# 11_-_GMAC1-SODIMM.net
KiCad netlist of a schematic drawn in Altium Designer
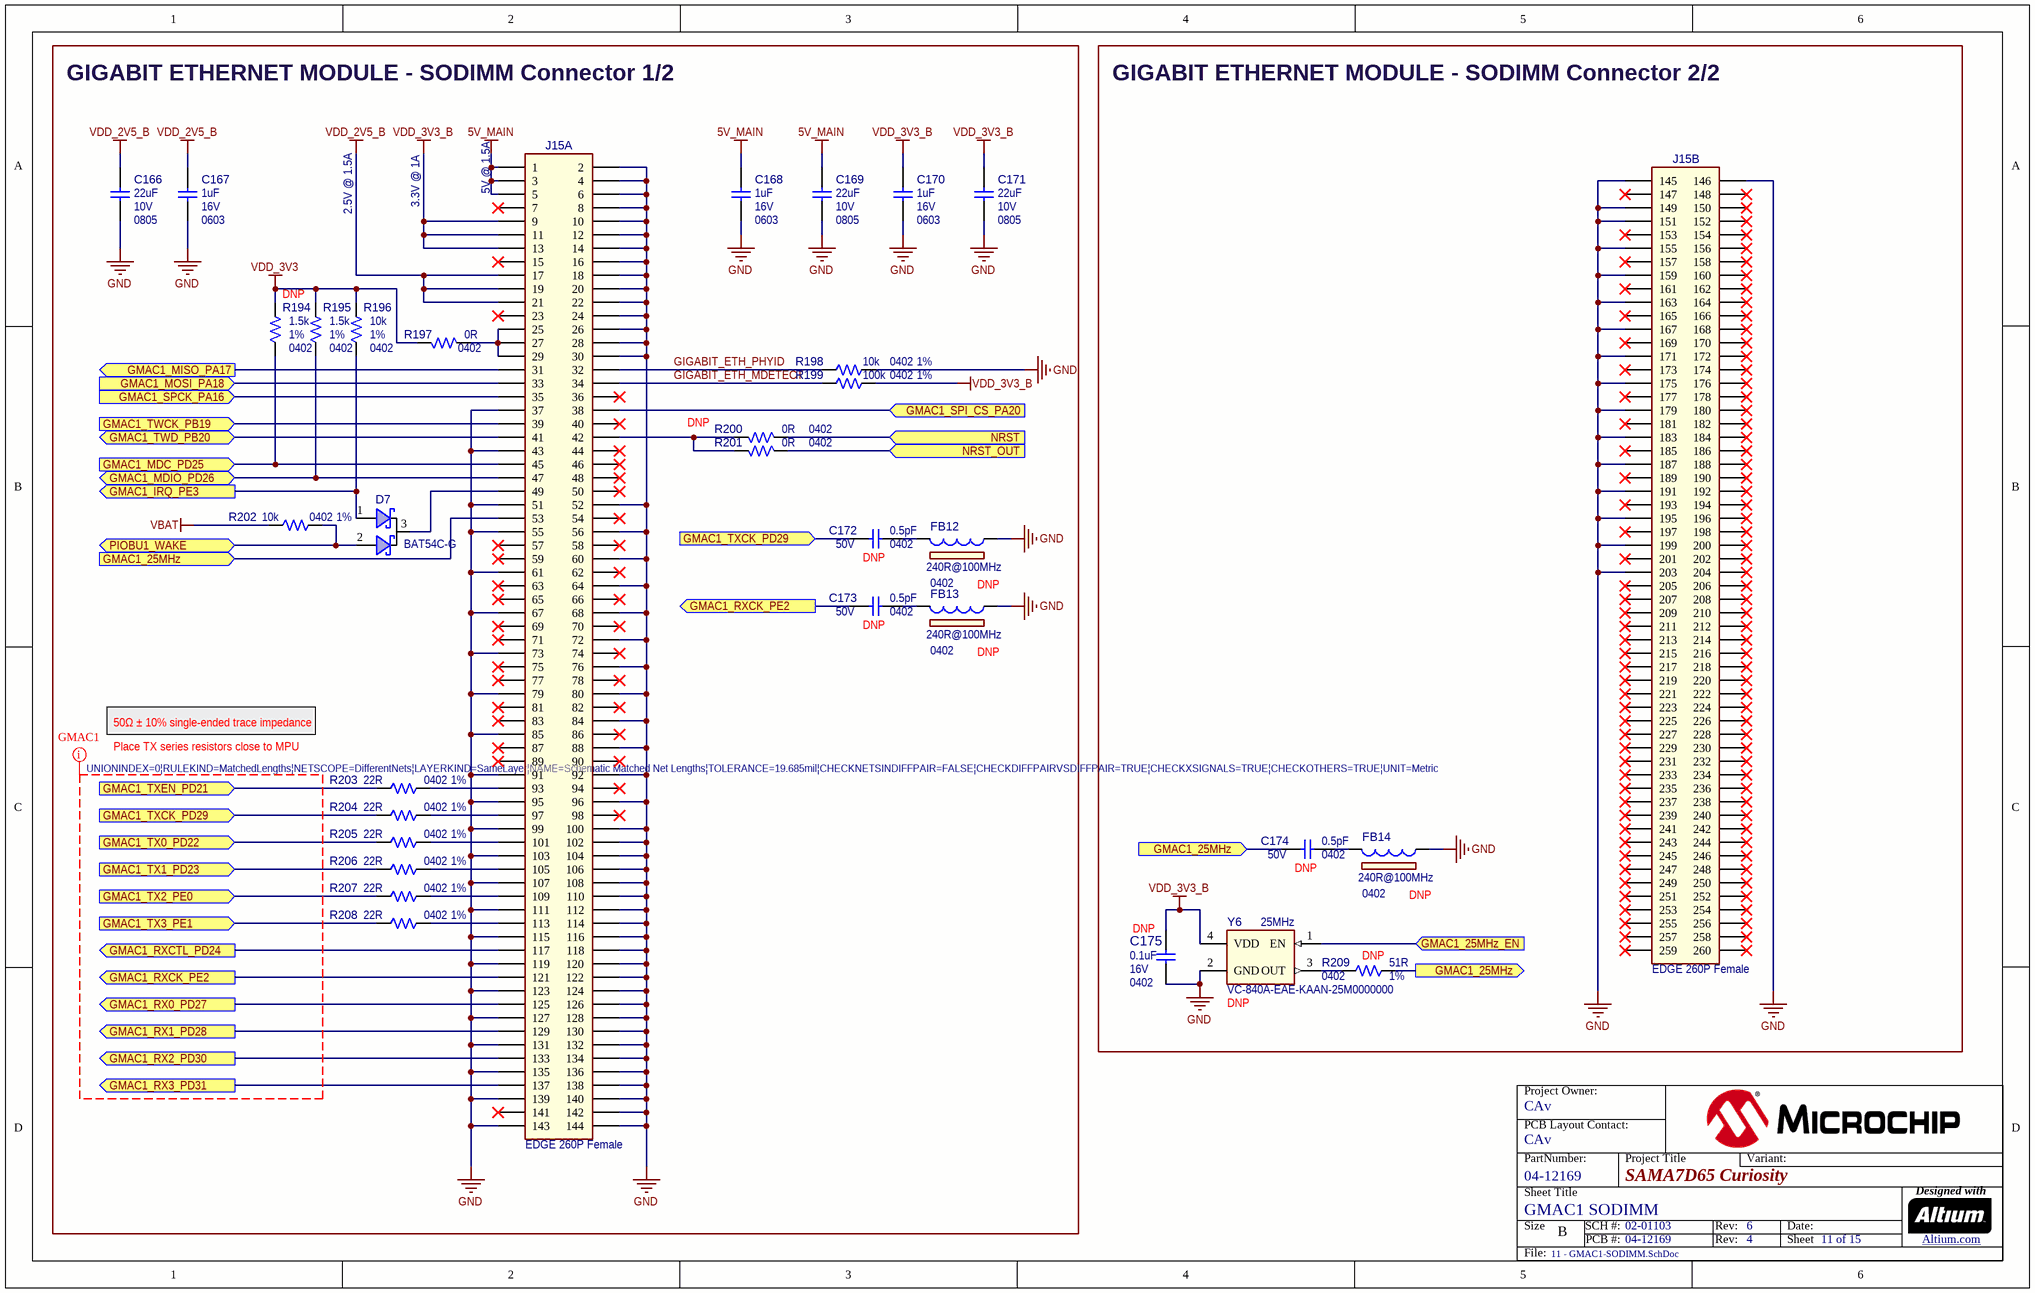
[diagram p0: 11 - GMAC1-SODIMM.SchDoc]

(export (version "E")
  (design (tool "Eeschema 10.0.6"))
  (components
    (comp (ref "C166")
      (value "22uF")
      (footprint "CAP_C_0805")
      (fields
        (field (name "VOLTAGE") "10V")
        (field (name "PACKAGE") "0805")
        (field (name "TOLERANCE") "20%")
        (field (name "Comment") "Capacitor NP")
        (field (name "OWNER") "Razvan Cristescu")
      )
      (libsource (lib "MCHP-CDB") (part "Capacitor NP"))
    )
    (comp (ref "C167")
      (value "1uF")
      (footprint "CAP_C_0603")
      (fields
        (field (name "VOLTAGE") "16V")
        (field (name "PACKAGE") "0603")
        (field (name "TOLERANCE") "10%")
        (field (name "Comment") "Capacitor NP")
      )
      (libsource (lib "MCHP-CDB") (part "Capacitor NP"))
    )
    (comp (ref "C168")
      (value "1uF")
      (footprint "CAP_C_0603")
      (fields
        (field (name "VOLTAGE") "16V")
        (field (name "PACKAGE") "0603")
        (field (name "TOLERANCE") "10%")
        (field (name "Comment") "Capacitor NP")
      )
      (libsource (lib "MCHP-CDB") (part "Capacitor NP"))
    )
    (comp (ref "C169")
      (value "22uF")
      (footprint "CAP_C_0805")
      (fields
        (field (name "VOLTAGE") "10V")
        (field (name "PACKAGE") "0805")
        (field (name "TOLERANCE") "20%")
        (field (name "Comment") "Capacitor NP")
        (field (name "OWNER") "Razvan Cristescu")
      )
      (libsource (lib "MCHP-CDB") (part "Capacitor NP"))
    )
    (comp (ref "C170")
      (value "1uF")
      (footprint "CAP_C_0603")
      (fields
        (field (name "VOLTAGE") "16V")
        (field (name "PACKAGE") "0603")
        (field (name "TOLERANCE") "10%")
        (field (name "Comment") "Capacitor NP")
      )
      (libsource (lib "MCHP-CDB") (part "Capacitor NP"))
    )
    (comp (ref "C171")
      (value "22uF")
      (footprint "CAP_C_0805")
      (fields
        (field (name "VOLTAGE") "10V")
        (field (name "PACKAGE") "0805")
        (field (name "TOLERANCE") "20%")
        (field (name "Comment") "Capacitor NP")
        (field (name "OWNER") "Razvan Cristescu")
      )
      (libsource (lib "MCHP-CDB") (part "Capacitor NP"))
    )
    (comp (ref "C172")
      (value "0.5pF")
      (footprint "CAP_C_0402")
      (fields
        (field (name "VOLTAGE") "50V")
        (field (name "PACKAGE") "0402")
        (field (name "TOLERANCE") "0.25pF")
        (field (name "POPULATED") "DNP")
        (field (name "Comment") "Capacitor NP")
      )
      (libsource (lib "MCHP-CDB") (part "Capacitor NP"))
    )
    (comp (ref "C173")
      (value "0.5pF")
      (footprint "CAP_C_0402")
      (fields
        (field (name "VOLTAGE") "50V")
        (field (name "PACKAGE") "0402")
        (field (name "TOLERANCE") "0.25pF")
        (field (name "POPULATED") "DNP")
        (field (name "Comment") "Capacitor NP")
      )
      (libsource (lib "MCHP-CDB") (part "Capacitor NP"))
    )
    (comp (ref "C174")
      (value "0.5pF")
      (footprint "CAP_C_0402")
      (fields
        (field (name "VOLTAGE") "50V")
        (field (name "PACKAGE") "0402")
        (field (name "TOLERANCE") "0.25pF")
        (field (name "POPULATED") "DNP")
        (field (name "Comment") "Capacitor NP")
      )
      (libsource (lib "MCHP-CDB") (part "Capacitor NP"))
    )
    (comp (ref "C175")
      (value "0.1uF")
      (footprint "CAP_C_0402")
      (fields
        (field (name "VOLTAGE") "16V")
        (field (name "PACKAGE") "0402")
        (field (name "TOLERANCE") "10%")
        (field (name "POPULATED") "DNP")
        (field (name "Comment") "Capacitor NP")
        (field (name "OWNER") "Sompoch Loboonlert")
      )
      (libsource (lib "MCHP-CDB") (part "Capacitor NP"))
    )
    (comp (ref "D7")
      (value "BAT54C-G")
      (footprint "SOT-23-3")
      (fields
        (field (name "POWER") "225mW")
        (field (name "Comment") "Diode Schottky Dual CK")
        (field (name "OWNER") "Cristina Salanti")
      )
      (libsource (lib "MCHP-CDB") (part "Diode Schottky Dual CK"))
    )
    (comp (ref "FB12")
      (value "240R@100MHz")
      (footprint "IND_C_0402")
      (fields
        (field (name "PACKAGE") "0402")
        (field (name "POPULATED") "DNP")
        (field (name "Comment") "Ferrite Bead")
        (field (name "OWNER") "Joerg Buehrer")
      )
      (libsource (lib "MCHP-CDB") (part "Ferrite Bead"))
    )
    (comp (ref "FB13")
      (value "240R@100MHz")
      (footprint "IND_C_0402")
      (fields
        (field (name "PACKAGE") "0402")
        (field (name "POPULATED") "DNP")
        (field (name "Comment") "Ferrite Bead")
        (field (name "OWNER") "Joerg Buehrer")
      )
      (libsource (lib "MCHP-CDB") (part "Ferrite Bead"))
    )
    (comp (ref "FB14")
      (value "240R@100MHz")
      (footprint "IND_C_0402")
      (fields
        (field (name "PACKAGE") "0402")
        (field (name "POPULATED") "DNP")
        (field (name "Comment") "Ferrite Bead")
        (field (name "OWNER") "Joerg Buehrer")
      )
      (libsource (lib "MCHP-CDB") (part "Ferrite Bead"))
    )
    (comp (ref "J15")
      (value "EDGE 260P Female")
      (footprint "CON_EDGE-CARD_DDR4_260P_SODIMM_2309413")
      (fields (field (name "Comment") "Header 2x130 EDGE CARD") (field (name "OWNER") "Sam Charles"))
      (libsource (lib "MCHP-CDB") (part "Header 2x130 EDGE CARD"))
    )
    (comp (ref "R194")
      (value "1.5k")
      (footprint "RES_C_0402")
      (description "Resistor")
      (fields
        (field (name "PACKAGE") "0402")
        (field (name "TOLERANCE") "1%")
        (field (name "POWER") "1/10W")
        (field (name "POPULATED") "DNP")
        (field (name "OWNER") "Gabor Bihari")
      )
      (libsource (lib "") (part "Resistor_1"))
    )
    (comp (ref "R195")
      (value "1.5k")
      (footprint "RES_C_0402")
      (description "Resistor")
      (fields
        (field (name "PACKAGE") "0402")
        (field (name "TOLERANCE") "1%")
        (field (name "POWER") "1/10W")
        (field (name "OWNER") "Gabor Bihari")
      )
      (libsource (lib "") (part "Resistor_1"))
    )
    (comp (ref "R196")
      (value "10k")
      (footprint "RES_C_0402")
      (description "Resistor")
      (fields
        (field (name "PACKAGE") "0402")
        (field (name "TOLERANCE") "1%")
        (field (name "VOLTAGE") "50V")
        (field (name "POWER") "1/10W")
        (field (name "OWNER") "Brent Lanphear")
      )
      (libsource (lib "MCHP-CDB") (part "Resistor"))
    )
    (comp (ref "R197")
      (value "0R")
      (footprint "RES_C_0402")
      (description "Resistor")
      (fields
        (field (name "PACKAGE") "0402")
        (field (name "POWER") "1/16W")
        (field (name "OWNER") "Sompoch Loboonlert")
      )
      (libsource (lib "") (part "Resistor_1"))
    )
    (comp (ref "R198")
      (value "10k")
      (footprint "RES_C_0402")
      (description "Resistor")
      (fields
        (field (name "PACKAGE") "0402")
        (field (name "TOLERANCE") "1%")
        (field (name "VOLTAGE") "50V")
        (field (name "POWER") "1/10W")
        (field (name "OWNER") "Brent Lanphear")
      )
      (libsource (lib "MCHP-CDB") (part "Resistor"))
    )
    (comp (ref "R199")
      (value "100k")
      (footprint "RES_C_0402")
      (description "Resistor")
      (fields
        (field (name "PACKAGE") "0402")
        (field (name "TOLERANCE") "1%")
        (field (name "VOLTAGE") "50V")
        (field (name "POWER") "1/10W")
        (field (name "OWNER") "Tad Ahlvers")
      )
      (libsource (lib "") (part "Resistor_1"))
    )
    (comp (ref "R200")
      (value "0R")
      (footprint "RES_C_0402")
      (description "Resistor")
      (fields
        (field (name "PACKAGE") "0402")
        (field (name "POWER") "1/16W")
        (field (name "POPULATED") "DNP")
        (field (name "OWNER") "Sompoch Loboonlert")
      )
      (libsource (lib "") (part "Resistor_1"))
    )
    (comp (ref "R201")
      (value "0R")
      (footprint "RES_C_0402")
      (description "Resistor")
      (fields
        (field (name "PACKAGE") "0402")
        (field (name "POWER") "1/16W")
        (field (name "OWNER") "Sompoch Loboonlert")
      )
      (libsource (lib "") (part "Resistor_1"))
    )
    (comp (ref "R202")
      (value "10k")
      (footprint "RES_C_0402")
      (description "Resistor")
      (fields
        (field (name "PACKAGE") "0402")
        (field (name "TOLERANCE") "1%")
        (field (name "VOLTAGE") "50V")
        (field (name "POWER") "1/10W")
        (field (name "OWNER") "Brent Lanphear")
      )
      (libsource (lib "MCHP-CDB") (part "Resistor"))
    )
    (comp (ref "R203")
      (value "22R")
      (footprint "RES_C_0402")
      (description "Resistor")
      (fields
        (field (name "PACKAGE") "0402")
        (field (name "TOLERANCE") "1%")
        (field (name "POWER") "1/10W")
        (field (name "OWNER") "Mike Ragsdale")
      )
      (libsource (lib "MCHP-CDB") (part "Resistor"))
    )
    (comp (ref "R204")
      (value "22R")
      (footprint "RES_C_0402")
      (description "Resistor")
      (fields
        (field (name "PACKAGE") "0402")
        (field (name "TOLERANCE") "1%")
        (field (name "POWER") "1/10W")
        (field (name "OWNER") "Mike Ragsdale")
      )
      (libsource (lib "MCHP-CDB") (part "Resistor"))
    )
    (comp (ref "R205")
      (value "22R")
      (footprint "RES_C_0402")
      (description "Resistor")
      (fields
        (field (name "PACKAGE") "0402")
        (field (name "TOLERANCE") "1%")
        (field (name "POWER") "1/10W")
        (field (name "OWNER") "Mike Ragsdale")
      )
      (libsource (lib "MCHP-CDB") (part "Resistor"))
    )
    (comp (ref "R206")
      (value "22R")
      (footprint "RES_C_0402")
      (description "Resistor")
      (fields
        (field (name "PACKAGE") "0402")
        (field (name "TOLERANCE") "1%")
        (field (name "POWER") "1/10W")
        (field (name "OWNER") "Mike Ragsdale")
      )
      (libsource (lib "MCHP-CDB") (part "Resistor"))
    )
    (comp (ref "R207")
      (value "22R")
      (footprint "RES_C_0402")
      (description "Resistor")
      (fields
        (field (name "PACKAGE") "0402")
        (field (name "TOLERANCE") "1%")
        (field (name "POWER") "1/10W")
        (field (name "OWNER") "Mike Ragsdale")
      )
      (libsource (lib "MCHP-CDB") (part "Resistor"))
    )
    (comp (ref "R208")
      (value "22R")
      (footprint "RES_C_0402")
      (description "Resistor")
      (fields
        (field (name "PACKAGE") "0402")
        (field (name "TOLERANCE") "1%")
        (field (name "POWER") "1/10W")
        (field (name "OWNER") "Mike Ragsdale")
      )
      (libsource (lib "MCHP-CDB") (part "Resistor"))
    )
    (comp (ref "R209")
      (value "51R")
      (footprint "RES_C_0402")
      (description "Resistor")
      (fields
        (field (name "PACKAGE") "0402")
        (field (name "TOLERANCE") "1%")
        (field (name "VOLTAGE") "50V")
        (field (name "POWER") "1/5W")
        (field (name "POPULATED") "DNP")
        (field (name "OWNER") "Dragos Danaila")
      )
      (libsource (lib "MCHP-CDB") (part "Resistor"))
    )
    (comp (ref "Y6")
      (value "25MHz")
      (footprint "CRYSTAL_VC-840")
      (fields
        (field (name "MANUFACTURER PART NUMBER 1") "VC-840A-EAE-KAAN-25M0000000")
        (field (name "POPULATED") "DNP")
        (field (name "Comment") "OSCILLATOR 4 Pins")
        (field (name "OWNER") "Pilar Alcaine")
      )
      (libsource (lib "MCHP-CDB") (part "OSCILLATOR 4 Pins"))
    )
  )
  (nets
    (net (code "1") (name "/GIGABIT_ETH_MDETECT") (class "Default")
      (node (ref "J15") (pin "34") (pinfunction "34_34") (pintype "passive"))
      (node (ref "R199") (pin "2") (pinfunction "2_2") (pintype "passive"))
    )
    (net (code "2") (name "/GIGABIT_ETH_PHYID") (class "Default")
      (node (ref "J15") (pin "32") (pinfunction "32_32") (pintype "passive"))
      (node (ref "R198") (pin "2") (pinfunction "2_2") (pintype "passive"))
    )
    (net (code "3") (name "/GMAC1_25MHz") (class "Default")
      (node (ref "C174") (pin "2") (pinfunction "2_2") (pintype "passive"))
      (node (ref "J15") (pin "53") (pinfunction "53_53") (pintype "passive"))
      (node (ref "R209") (pin "1") (pinfunction "1_1") (pintype "passive"))
    )
    (net (code "4") (name "/GMAC1_25MHz_EN") (class "Default")
      (node (ref "Y6") (pin "1") (pinfunction "EN_1") (pintype "input"))
    )
    (net (code "5") (name "/GMAC1_IRQ_PE3") (class "Default")
      (node (ref "D7") (pin "1") (pinfunction "A_1") (pintype "passive"))
      (node (ref "R196") (pin "1") (pinfunction "1_1") (pintype "passive"))
    )
    (net (code "6") (name "/GMAC1_MDC_PD25") (class "Default")
      (node (ref "J15") (pin "45") (pinfunction "45_45") (pintype "passive"))
      (node (ref "R194") (pin "1") (pinfunction "1_1") (pintype "passive"))
    )
    (net (code "7") (name "/GMAC1_MDIO_PD26") (class "Default")
      (node (ref "J15") (pin "47") (pinfunction "47_47") (pintype "passive"))
      (node (ref "R195") (pin "1") (pinfunction "1_1") (pintype "passive"))
    )
    (net (code "8") (name "/GMAC1_MISO_PA17") (class "Default")
      (node (ref "J15") (pin "31") (pinfunction "31_31") (pintype "passive"))
    )
    (net (code "9") (name "/GMAC1_MOSI_PA18") (class "Default")
      (node (ref "J15") (pin "33") (pinfunction "33_33") (pintype "passive"))
    )
    (net (code "10") (name "/GMAC1_RX0_PD27") (class "Default")
      (node (ref "J15") (pin "125") (pinfunction "125_125") (pintype "passive"))
    )
    (net (code "11") (name "/GMAC1_RX1_PD28") (class "Default")
      (node (ref "J15") (pin "129") (pinfunction "129_129") (pintype "passive"))
    )
    (net (code "12") (name "/GMAC1_RX2_PD30") (class "Default")
      (node (ref "J15") (pin "133") (pinfunction "133_133") (pintype "passive"))
    )
    (net (code "13") (name "/GMAC1_RX3_PD31") (class "Default")
      (node (ref "J15") (pin "137") (pinfunction "137_137") (pintype "passive"))
    )
    (net (code "14") (name "/GMAC1_RXCK_PE2") (class "Default")
      (node (ref "C173") (pin "2") (pinfunction "2_2") (pintype "passive"))
      (node (ref "J15") (pin "121") (pinfunction "121_121") (pintype "passive"))
    )
    (net (code "15") (name "/GMAC1_RXCTL_PD24") (class "Default")
      (node (ref "J15") (pin "117") (pinfunction "117_117") (pintype "passive"))
    )
    (net (code "16") (name "/GMAC1_SPCK_PA16") (class "Default")
      (node (ref "J15") (pin "35") (pinfunction "35_35") (pintype "passive"))
    )
    (net (code "17") (name "/GMAC1_SPI_CS_PA20") (class "Default")
      (node (ref "J15") (pin "38") (pinfunction "38_38") (pintype "passive"))
    )
    (net (code "18") (name "/GMAC1_TWCK_PB19") (class "Default")
      (node (ref "J15") (pin "39") (pinfunction "39_39") (pintype "passive"))
    )
    (net (code "19") (name "/GMAC1_TWD_PB20") (class "Default")
      (node (ref "J15") (pin "41") (pinfunction "41_41") (pintype "passive"))
    )
    (net (code "20") (name "/GMAC1_TX0_PD22") (class "Default")
      (node (ref "R205") (pin "1") (pinfunction "1_1") (pintype "passive"))
    )
    (net (code "21") (name "/GMAC1_TX1_PD23") (class "Default")
      (node (ref "R206") (pin "1") (pinfunction "1_1") (pintype "passive"))
    )
    (net (code "22") (name "/GMAC1_TX2_PE0") (class "Default")
      (node (ref "R207") (pin "1") (pinfunction "1_1") (pintype "passive"))
    )
    (net (code "23") (name "/GMAC1_TX3_PE1") (class "Default")
      (node (ref "R208") (pin "1") (pinfunction "1_1") (pintype "passive"))
    )
    (net (code "24") (name "/GMAC1_TXCK_PD29") (class "Default")
      (node (ref "C172") (pin "2") (pinfunction "2_2") (pintype "passive"))
      (node (ref "R204") (pin "1") (pinfunction "1_1") (pintype "passive"))
    )
    (net (code "25") (name "/GMAC1_TXEN_PD21") (class "Default")
      (node (ref "R203") (pin "1") (pinfunction "1_1") (pintype "passive"))
    )
    (net (code "26") (name "/NRST") (class "Default")
      (node (ref "R200") (pin "2") (pinfunction "2_2") (pintype "passive"))
    )
    (net (code "27") (name "/NRST_OUT") (class "Default")
      (node (ref "R201") (pin "2") (pinfunction "2_2") (pintype "passive"))
    )
    (net (code "28") (name "/PIOBU1_WAKE") (class "Default")
      (node (ref "D7") (pin "2") (pinfunction "A_2") (pintype "passive"))
      (node (ref "R202") (pin "1") (pinfunction "1_1") (pintype "passive"))
    )
    (net (code "29") (name "5V_MAIN") (class "Default")
      (node (ref "C168") (pin "2") (pinfunction "2_2") (pintype "passive"))
      (node (ref "C169") (pin "2") (pinfunction "2_2") (pintype "passive"))
      (node (ref "J15") (pin "1") (pinfunction "1_1") (pintype "passive"))
      (node (ref "J15") (pin "3") (pinfunction "3_3") (pintype "passive"))
      (node (ref "J15") (pin "5") (pinfunction "5_5") (pintype "passive"))
    )
    (net (code "30") (name "GND") (class "Default")
      (node (ref "C166") (pin "1") (pinfunction "1_1") (pintype "passive"))
      (node (ref "C167") (pin "2") (pinfunction "2_2") (pintype "passive"))
      (node (ref "C168") (pin "1") (pinfunction "1_1") (pintype "passive"))
      (node (ref "C169") (pin "1") (pinfunction "1_1") (pintype "passive"))
      (node (ref "C170") (pin "1") (pinfunction "1_1") (pintype "passive"))
      (node (ref "C171") (pin "1") (pinfunction "1_1") (pintype "passive"))
      (node (ref "C175") (pin "1") (pinfunction "1_1") (pintype "passive"))
      (node (ref "FB12") (pin "1") (pinfunction "1_1") (pintype "passive"))
      (node (ref "FB13") (pin "1") (pinfunction "1_1") (pintype "passive"))
      (node (ref "FB14") (pin "1") (pinfunction "1_1") (pintype "passive"))
      (node (ref "J15") (pin "10") (pinfunction "10_10") (pintype "passive"))
      (node (ref "J15") (pin "100") (pinfunction "100_100") (pintype "passive"))
      (node (ref "J15") (pin "102") (pinfunction "102_102") (pintype "passive"))
      (node (ref "J15") (pin "103") (pinfunction "103_103") (pintype "passive"))
      (node (ref "J15") (pin "104") (pinfunction "104_104") (pintype "passive"))
      (node (ref "J15") (pin "106") (pinfunction "106_106") (pintype "passive"))
      (node (ref "J15") (pin "107") (pinfunction "107_107") (pintype "passive"))
      (node (ref "J15") (pin "108") (pinfunction "108_108") (pintype "passive"))
      (node (ref "J15") (pin "110") (pinfunction "110_110") (pintype "passive"))
      (node (ref "J15") (pin "111") (pinfunction "111_111") (pintype "passive"))
      (node (ref "J15") (pin "112") (pinfunction "112_112") (pintype "passive"))
      (node (ref "J15") (pin "114") (pinfunction "114_114") (pintype "passive"))
      (node (ref "J15") (pin "115") (pinfunction "115_115") (pintype "passive"))
      (node (ref "J15") (pin "116") (pinfunction "116_116") (pintype "passive"))
      (node (ref "J15") (pin "118") (pinfunction "118_118") (pintype "passive"))
      (node (ref "J15") (pin "119") (pinfunction "119_119") (pintype "passive"))
      (node (ref "J15") (pin "12") (pinfunction "12_12") (pintype "passive"))
      (node (ref "J15") (pin "120") (pinfunction "120_120") (pintype "passive"))
      (node (ref "J15") (pin "122") (pinfunction "122_122") (pintype "passive"))
      (node (ref "J15") (pin "123") (pinfunction "123_123") (pintype "passive"))
      (node (ref "J15") (pin "124") (pinfunction "124_124") (pintype "passive"))
      (node (ref "J15") (pin "126") (pinfunction "126_126") (pintype "passive"))
      (node (ref "J15") (pin "127") (pinfunction "127_127") (pintype "passive"))
      (node (ref "J15") (pin "128") (pinfunction "128_128") (pintype "passive"))
      (node (ref "J15") (pin "130") (pinfunction "130_130") (pintype "passive"))
      (node (ref "J15") (pin "131") (pinfunction "131_131") (pintype "passive"))
      (node (ref "J15") (pin "132") (pinfunction "132_132") (pintype "passive"))
      (node (ref "J15") (pin "134") (pinfunction "134_134") (pintype "passive"))
      (node (ref "J15") (pin "135") (pinfunction "135_135") (pintype "passive"))
      (node (ref "J15") (pin "136") (pinfunction "136_136") (pintype "passive"))
      (node (ref "J15") (pin "138") (pinfunction "138_138") (pintype "passive"))
      (node (ref "J15") (pin "139") (pinfunction "139_139") (pintype "passive"))
      (node (ref "J15") (pin "14") (pinfunction "14_14") (pintype "passive"))
      (node (ref "J15") (pin "140") (pinfunction "140_140") (pintype "passive"))
      (node (ref "J15") (pin "142") (pinfunction "142_142") (pintype "passive"))
      (node (ref "J15") (pin "143") (pinfunction "143_143") (pintype "passive"))
      (node (ref "J15") (pin "144") (pinfunction "144_144") (pintype "passive"))
      (node (ref "J15") (pin "145") (pinfunction "145_145") (pintype "passive"))
      (node (ref "J15") (pin "146") (pinfunction "146_146") (pintype "passive"))
      (node (ref "J15") (pin "149") (pinfunction "149_149") (pintype "passive"))
      (node (ref "J15") (pin "151") (pinfunction "151_151") (pintype "passive"))
      (node (ref "J15") (pin "155") (pinfunction "155_155") (pintype "passive"))
      (node (ref "J15") (pin "159") (pinfunction "159_159") (pintype "passive"))
      (node (ref "J15") (pin "16") (pinfunction "16_16") (pintype "passive"))
      (node (ref "J15") (pin "163") (pinfunction "163_163") (pintype "passive"))
      (node (ref "J15") (pin "167") (pinfunction "167_167") (pintype "passive"))
      (node (ref "J15") (pin "171") (pinfunction "171_171") (pintype "passive"))
      (node (ref "J15") (pin "175") (pinfunction "175_175") (pintype "passive"))
      (node (ref "J15") (pin "179") (pinfunction "179_179") (pintype "passive"))
      (node (ref "J15") (pin "18") (pinfunction "18_18") (pintype "passive"))
      (node (ref "J15") (pin "183") (pinfunction "183_183") (pintype "passive"))
      (node (ref "J15") (pin "187") (pinfunction "187_187") (pintype "passive"))
      (node (ref "J15") (pin "191") (pinfunction "191_191") (pintype "passive"))
      (node (ref "J15") (pin "195") (pinfunction "195_195") (pintype "passive"))
      (node (ref "J15") (pin "199") (pinfunction "199_199") (pintype "passive"))
      (node (ref "J15") (pin "2") (pinfunction "2_2") (pintype "passive"))
      (node (ref "J15") (pin "20") (pinfunction "20_20") (pintype "passive"))
      (node (ref "J15") (pin "203") (pinfunction "203_203") (pintype "passive"))
      (node (ref "J15") (pin "22") (pinfunction "22_22") (pintype "passive"))
      (node (ref "J15") (pin "24") (pinfunction "24_24") (pintype "passive"))
      (node (ref "J15") (pin "26") (pinfunction "26_26") (pintype "passive"))
      (node (ref "J15") (pin "28") (pinfunction "28_28") (pintype "passive"))
      (node (ref "J15") (pin "30") (pinfunction "30_30") (pintype "passive"))
      (node (ref "J15") (pin "37") (pinfunction "37_37") (pintype "passive"))
      (node (ref "J15") (pin "4") (pinfunction "4_4") (pintype "passive"))
      (node (ref "J15") (pin "43") (pinfunction "43_43") (pintype "passive"))
      (node (ref "J15") (pin "51") (pinfunction "51_51") (pintype "passive"))
      (node (ref "J15") (pin "52") (pinfunction "52_52") (pintype "passive"))
      (node (ref "J15") (pin "55") (pinfunction "55_55") (pintype "passive"))
      (node (ref "J15") (pin "56") (pinfunction "56_56") (pintype "passive"))
      (node (ref "J15") (pin "6") (pinfunction "6_6") (pintype "passive"))
      (node (ref "J15") (pin "60") (pinfunction "60_60") (pintype "passive"))
      (node (ref "J15") (pin "61") (pinfunction "61_61") (pintype "passive"))
      (node (ref "J15") (pin "64") (pinfunction "64_64") (pintype "passive"))
      (node (ref "J15") (pin "67") (pinfunction "67_67") (pintype "passive"))
      (node (ref "J15") (pin "68") (pinfunction "68_68") (pintype "passive"))
      (node (ref "J15") (pin "72") (pinfunction "72_72") (pintype "passive"))
      (node (ref "J15") (pin "73") (pinfunction "73_73") (pintype "passive"))
      (node (ref "J15") (pin "76") (pinfunction "76_76") (pintype "passive"))
      (node (ref "J15") (pin "79") (pinfunction "79_79") (pintype "passive"))
      (node (ref "J15") (pin "8") (pinfunction "8_8") (pintype "passive"))
      (node (ref "J15") (pin "80") (pinfunction "80_80") (pintype "passive"))
      (node (ref "J15") (pin "84") (pinfunction "84_84") (pintype "passive"))
      (node (ref "J15") (pin "85") (pinfunction "85_85") (pintype "passive"))
      (node (ref "J15") (pin "88") (pinfunction "88_88") (pintype "passive"))
      (node (ref "J15") (pin "91") (pinfunction "91_91") (pintype "passive"))
      (node (ref "J15") (pin "92") (pinfunction "92_92") (pintype "passive"))
      (node (ref "J15") (pin "95") (pinfunction "95_95") (pintype "passive"))
      (node (ref "J15") (pin "96") (pinfunction "96_96") (pintype "passive"))
      (node (ref "J15") (pin "99") (pinfunction "99_99") (pintype "passive"))
      (node (ref "R198") (pin "1") (pinfunction "1_1") (pintype "passive"))
      (node (ref "Y6") (pin "2") (pinfunction "GND_2") (pintype "power_in"))
    )
    (net (code "31") (name "Net-(C172-Pad1)") (class "Default")
      (node (ref "C172") (pin "1") (pinfunction "1_1") (pintype "passive"))
      (node (ref "FB12") (pin "2") (pinfunction "2_2") (pintype "passive"))
    )
    (net (code "32") (name "Net-(C173-Pad1)") (class "Default")
      (node (ref "C173") (pin "1") (pinfunction "1_1") (pintype "passive"))
      (node (ref "FB13") (pin "2") (pinfunction "2_2") (pintype "passive"))
    )
    (net (code "33") (name "Net-(C174-Pad1)") (class "Default")
      (node (ref "C174") (pin "1") (pinfunction "1_1") (pintype "passive"))
      (node (ref "FB14") (pin "2") (pinfunction "2_2") (pintype "passive"))
    )
    (net (code "34") (name "Net-(D7-KK)") (class "Default")
      (node (ref "D7") (pin "3") (pinfunction "KK_3") (pintype "passive"))
      (node (ref "J15") (pin "49") (pinfunction "49_49") (pintype "passive"))
    )
    (net (code "35") (name "Net-(J15-Pad25)") (class "Default")
      (node (ref "J15") (pin "25") (pinfunction "25_25") (pintype "passive"))
      (node (ref "J15") (pin "27") (pinfunction "27_27") (pintype "passive"))
      (node (ref "J15") (pin "29") (pinfunction "29_29") (pintype "passive"))
      (node (ref "R197") (pin "2") (pinfunction "2_2") (pintype "passive"))
    )
    (net (code "36") (name "Net-(J15-Pad42)") (class "Default")
      (node (ref "J15") (pin "42") (pinfunction "42_42") (pintype "passive"))
      (node (ref "R200") (pin "1") (pinfunction "1_1") (pintype "passive"))
      (node (ref "R201") (pin "1") (pinfunction "1_1") (pintype "passive"))
    )
    (net (code "37") (name "Net-(J15-Pad93)") (class "Default")
      (node (ref "J15") (pin "93") (pinfunction "93_93") (pintype "passive"))
      (node (ref "R203") (pin "2") (pinfunction "2_2") (pintype "passive"))
    )
    (net (code "38") (name "Net-(J15-Pad97)") (class "Default")
      (node (ref "J15") (pin "97") (pinfunction "97_97") (pintype "passive"))
      (node (ref "R204") (pin "2") (pinfunction "2_2") (pintype "passive"))
    )
    (net (code "39") (name "Net-(J15-Pad101)") (class "Default")
      (node (ref "J15") (pin "101") (pinfunction "101_101") (pintype "passive"))
      (node (ref "R205") (pin "2") (pinfunction "2_2") (pintype "passive"))
    )
    (net (code "40") (name "Net-(J15-Pad105)") (class "Default")
      (node (ref "J15") (pin "105") (pinfunction "105_105") (pintype "passive"))
      (node (ref "R206") (pin "2") (pinfunction "2_2") (pintype "passive"))
    )
    (net (code "41") (name "Net-(J15-Pad109)") (class "Default")
      (node (ref "J15") (pin "109") (pinfunction "109_109") (pintype "passive"))
      (node (ref "R207") (pin "2") (pinfunction "2_2") (pintype "passive"))
    )
    (net (code "42") (name "Net-(J15-Pad113)") (class "Default")
      (node (ref "J15") (pin "113") (pinfunction "113_113") (pintype "passive"))
      (node (ref "R208") (pin "2") (pinfunction "2_2") (pintype "passive"))
    )
    (net (code "43") (name "Net-(Y6-OUT)") (class "Default")
      (node (ref "R209") (pin "2") (pinfunction "2_2") (pintype "passive"))
      (node (ref "Y6") (pin "3") (pinfunction "OUT_3") (pintype "output"))
    )
    (net (code "44") (name "VBAT") (class "Default")
      (node (ref "R202") (pin "2") (pinfunction "2_2") (pintype "passive"))
    )
    (net (code "45") (name "VDD_2V5_B") (class "Default")
      (node (ref "C166") (pin "2") (pinfunction "2_2") (pintype "passive"))
      (node (ref "C167") (pin "1") (pinfunction "1_1") (pintype "passive"))
      (node (ref "J15") (pin "17") (pinfunction "17_17") (pintype "passive"))
      (node (ref "J15") (pin "19") (pinfunction "19_19") (pintype "passive"))
      (node (ref "J15") (pin "21") (pinfunction "21_21") (pintype "passive"))
    )
    (net (code "46") (name "VDD_3V3") (class "Default")
      (node (ref "R194") (pin "2") (pinfunction "2_2") (pintype "passive"))
      (node (ref "R195") (pin "2") (pinfunction "2_2") (pintype "passive"))
      (node (ref "R196") (pin "2") (pinfunction "2_2") (pintype "passive"))
      (node (ref "R197") (pin "1") (pinfunction "1_1") (pintype "passive"))
    )
    (net (code "47") (name "VDD_3V3_B") (class "Default")
      (node (ref "C170") (pin "2") (pinfunction "2_2") (pintype "passive"))
      (node (ref "C171") (pin "2") (pinfunction "2_2") (pintype "passive"))
      (node (ref "C175") (pin "2") (pinfunction "2_2") (pintype "passive"))
      (node (ref "J15") (pin "11") (pinfunction "11_11") (pintype "passive"))
      (node (ref "J15") (pin "13") (pinfunction "13_13") (pintype "passive"))
      (node (ref "J15") (pin "9") (pinfunction "9_9") (pintype "passive"))
      (node (ref "R199") (pin "1") (pinfunction "1_1") (pintype "passive"))
      (node (ref "Y6") (pin "4") (pinfunction "VDD_4") (pintype "power_in"))
    )
    (net (code "48") (name "unconnected-(J15-Pad7)") (class "Default")
      (node (ref "J15") (pin "7") (pinfunction "7_7") (pintype "passive+no_connect"))
    )
    (net (code "49") (name "unconnected-(J15-Pad15)") (class "Default")
      (node (ref "J15") (pin "15") (pinfunction "15_15") (pintype "passive+no_connect"))
    )
    (net (code "50") (name "unconnected-(J15-Pad23)") (class "Default")
      (node (ref "J15") (pin "23") (pinfunction "23_23") (pintype "passive+no_connect"))
    )
    (net (code "51") (name "unconnected-(J15-Pad36)") (class "Default")
      (node (ref "J15") (pin "36") (pinfunction "36_36") (pintype "passive+no_connect"))
    )
    (net (code "52") (name "unconnected-(J15-Pad40)") (class "Default")
      (node (ref "J15") (pin "40") (pinfunction "40_40") (pintype "passive+no_connect"))
    )
    (net (code "53") (name "unconnected-(J15-Pad44)") (class "Default")
      (node (ref "J15") (pin "44") (pinfunction "44_44") (pintype "passive+no_connect"))
    )
    (net (code "54") (name "unconnected-(J15-Pad46)") (class "Default")
      (node (ref "J15") (pin "46") (pinfunction "46_46") (pintype "passive+no_connect"))
    )
    (net (code "55") (name "unconnected-(J15-Pad48)") (class "Default")
      (node (ref "J15") (pin "48") (pinfunction "48_48") (pintype "passive+no_connect"))
    )
    (net (code "56") (name "unconnected-(J15-Pad50)") (class "Default")
      (node (ref "J15") (pin "50") (pinfunction "50_50") (pintype "passive+no_connect"))
    )
    (net (code "57") (name "unconnected-(J15-Pad54)") (class "Default")
      (node (ref "J15") (pin "54") (pinfunction "54_54") (pintype "passive+no_connect"))
    )
    (net (code "58") (name "unconnected-(J15-Pad57)") (class "Default")
      (node (ref "J15") (pin "57") (pinfunction "57_57") (pintype "passive+no_connect"))
    )
    (net (code "59") (name "unconnected-(J15-Pad58)") (class "Default")
      (node (ref "J15") (pin "58") (pinfunction "58_58") (pintype "passive+no_connect"))
    )
    (net (code "60") (name "unconnected-(J15-Pad59)") (class "Default")
      (node (ref "J15") (pin "59") (pinfunction "59_59") (pintype "passive+no_connect"))
    )
    (net (code "61") (name "unconnected-(J15-Pad62)") (class "Default")
      (node (ref "J15") (pin "62") (pinfunction "62_62") (pintype "passive+no_connect"))
    )
    (net (code "62") (name "unconnected-(J15-Pad63)") (class "Default")
      (node (ref "J15") (pin "63") (pinfunction "63_63") (pintype "passive+no_connect"))
    )
    (net (code "63") (name "unconnected-(J15-Pad65)") (class "Default")
      (node (ref "J15") (pin "65") (pinfunction "65_65") (pintype "passive+no_connect"))
    )
    (net (code "64") (name "unconnected-(J15-Pad66)") (class "Default")
      (node (ref "J15") (pin "66") (pinfunction "66_66") (pintype "passive+no_connect"))
    )
    (net (code "65") (name "unconnected-(J15-Pad69)") (class "Default")
      (node (ref "J15") (pin "69") (pinfunction "69_69") (pintype "passive+no_connect"))
    )
    (net (code "66") (name "unconnected-(J15-Pad70)") (class "Default")
      (node (ref "J15") (pin "70") (pinfunction "70_70") (pintype "passive+no_connect"))
    )
    (net (code "67") (name "unconnected-(J15-Pad71)") (class "Default")
      (node (ref "J15") (pin "71") (pinfunction "71_71") (pintype "passive+no_connect"))
    )
    (net (code "68") (name "unconnected-(J15-Pad74)") (class "Default")
      (node (ref "J15") (pin "74") (pinfunction "74_74") (pintype "passive+no_connect"))
    )
    (net (code "69") (name "unconnected-(J15-Pad75)") (class "Default")
      (node (ref "J15") (pin "75") (pinfunction "75_75") (pintype "passive+no_connect"))
    )
    (net (code "70") (name "unconnected-(J15-Pad77)") (class "Default")
      (node (ref "J15") (pin "77") (pinfunction "77_77") (pintype "passive+no_connect"))
    )
    (net (code "71") (name "unconnected-(J15-Pad78)") (class "Default")
      (node (ref "J15") (pin "78") (pinfunction "78_78") (pintype "passive+no_connect"))
    )
    (net (code "72") (name "unconnected-(J15-Pad81)") (class "Default")
      (node (ref "J15") (pin "81") (pinfunction "81_81") (pintype "passive+no_connect"))
    )
    (net (code "73") (name "unconnected-(J15-Pad82)") (class "Default")
      (node (ref "J15") (pin "82") (pinfunction "82_82") (pintype "passive+no_connect"))
    )
    (net (code "74") (name "unconnected-(J15-Pad83)") (class "Default")
      (node (ref "J15") (pin "83") (pinfunction "83_83") (pintype "passive+no_connect"))
    )
    (net (code "75") (name "unconnected-(J15-Pad86)") (class "Default")
      (node (ref "J15") (pin "86") (pinfunction "86_86") (pintype "passive+no_connect"))
    )
    (net (code "76") (name "unconnected-(J15-Pad87)") (class "Default")
      (node (ref "J15") (pin "87") (pinfunction "87_87") (pintype "passive+no_connect"))
    )
    (net (code "77") (name "unconnected-(J15-Pad89)") (class "Default")
      (node (ref "J15") (pin "89") (pinfunction "89_89") (pintype "passive+no_connect"))
    )
    (net (code "78") (name "unconnected-(J15-Pad90)") (class "Default")
      (node (ref "J15") (pin "90") (pinfunction "90_90") (pintype "passive+no_connect"))
    )
    (net (code "79") (name "unconnected-(J15-Pad94)") (class "Default")
      (node (ref "J15") (pin "94") (pinfunction "94_94") (pintype "passive+no_connect"))
    )
    (net (code "80") (name "unconnected-(J15-Pad98)") (class "Default")
      (node (ref "J15") (pin "98") (pinfunction "98_98") (pintype "passive+no_connect"))
    )
    (net (code "81") (name "unconnected-(J15-Pad141)") (class "Default")
      (node (ref "J15") (pin "141") (pinfunction "141_141") (pintype "passive+no_connect"))
    )
    (net (code "82") (name "unconnected-(J15-Pad147)") (class "Default")
      (node (ref "J15") (pin "147") (pinfunction "147_147") (pintype "passive+no_connect"))
    )
    (net (code "83") (name "unconnected-(J15-Pad148)") (class "Default")
      (node (ref "J15") (pin "148") (pinfunction "148_148") (pintype "passive+no_connect"))
    )
    (net (code "84") (name "unconnected-(J15-Pad150)") (class "Default")
      (node (ref "J15") (pin "150") (pinfunction "150_150") (pintype "passive+no_connect"))
    )
    (net (code "85") (name "unconnected-(J15-Pad152)") (class "Default")
      (node (ref "J15") (pin "152") (pinfunction "152_152") (pintype "passive+no_connect"))
    )
    (net (code "86") (name "unconnected-(J15-Pad153)") (class "Default")
      (node (ref "J15") (pin "153") (pinfunction "153_153") (pintype "passive+no_connect"))
    )
    (net (code "87") (name "unconnected-(J15-Pad154)") (class "Default")
      (node (ref "J15") (pin "154") (pinfunction "154_154") (pintype "passive+no_connect"))
    )
    (net (code "88") (name "unconnected-(J15-Pad156)") (class "Default")
      (node (ref "J15") (pin "156") (pinfunction "156_156") (pintype "passive+no_connect"))
    )
    (net (code "89") (name "unconnected-(J15-Pad157)") (class "Default")
      (node (ref "J15") (pin "157") (pinfunction "157_157") (pintype "passive+no_connect"))
    )
    (net (code "90") (name "unconnected-(J15-Pad158)") (class "Default")
      (node (ref "J15") (pin "158") (pinfunction "158_158") (pintype "passive+no_connect"))
    )
    (net (code "91") (name "unconnected-(J15-Pad160)") (class "Default")
      (node (ref "J15") (pin "160") (pinfunction "160_160") (pintype "passive+no_connect"))
    )
    (net (code "92") (name "unconnected-(J15-Pad161)") (class "Default")
      (node (ref "J15") (pin "161") (pinfunction "161_161") (pintype "passive+no_connect"))
    )
    (net (code "93") (name "unconnected-(J15-Pad162)") (class "Default")
      (node (ref "J15") (pin "162") (pinfunction "162_162") (pintype "passive+no_connect"))
    )
    (net (code "94") (name "unconnected-(J15-Pad164)") (class "Default")
      (node (ref "J15") (pin "164") (pinfunction "164_164") (pintype "passive+no_connect"))
    )
    (net (code "95") (name "unconnected-(J15-Pad165)") (class "Default")
      (node (ref "J15") (pin "165") (pinfunction "165_165") (pintype "passive+no_connect"))
    )
    (net (code "96") (name "unconnected-(J15-Pad166)") (class "Default")
      (node (ref "J15") (pin "166") (pinfunction "166_166") (pintype "passive+no_connect"))
    )
    (net (code "97") (name "unconnected-(J15-Pad168)") (class "Default")
      (node (ref "J15") (pin "168") (pinfunction "168_168") (pintype "passive+no_connect"))
    )
    (net (code "98") (name "unconnected-(J15-Pad169)") (class "Default")
      (node (ref "J15") (pin "169") (pinfunction "169_169") (pintype "passive+no_connect"))
    )
    (net (code "99") (name "unconnected-(J15-Pad170)") (class "Default")
      (node (ref "J15") (pin "170") (pinfunction "170_170") (pintype "passive+no_connect"))
    )
    (net (code "100") (name "unconnected-(J15-Pad172)") (class "Default")
      (node (ref "J15") (pin "172") (pinfunction "172_172") (pintype "passive+no_connect"))
    )
    (net (code "101") (name "unconnected-(J15-Pad173)") (class "Default")
      (node (ref "J15") (pin "173") (pinfunction "173_173") (pintype "passive+no_connect"))
    )
    (net (code "102") (name "unconnected-(J15-Pad174)") (class "Default")
      (node (ref "J15") (pin "174") (pinfunction "174_174") (pintype "passive+no_connect"))
    )
    (net (code "103") (name "unconnected-(J15-Pad176)") (class "Default")
      (node (ref "J15") (pin "176") (pinfunction "176_176") (pintype "passive+no_connect"))
    )
    (net (code "104") (name "unconnected-(J15-Pad177)") (class "Default")
      (node (ref "J15") (pin "177") (pinfunction "177_177") (pintype "passive+no_connect"))
    )
    (net (code "105") (name "unconnected-(J15-Pad178)") (class "Default")
      (node (ref "J15") (pin "178") (pinfunction "178_178") (pintype "passive+no_connect"))
    )
    (net (code "106") (name "unconnected-(J15-Pad180)") (class "Default")
      (node (ref "J15") (pin "180") (pinfunction "180_180") (pintype "passive+no_connect"))
    )
    (net (code "107") (name "unconnected-(J15-Pad181)") (class "Default")
      (node (ref "J15") (pin "181") (pinfunction "181_181") (pintype "passive+no_connect"))
    )
    (net (code "108") (name "unconnected-(J15-Pad182)") (class "Default")
      (node (ref "J15") (pin "182") (pinfunction "182_182") (pintype "passive+no_connect"))
    )
    (net (code "109") (name "unconnected-(J15-Pad184)") (class "Default")
      (node (ref "J15") (pin "184") (pinfunction "184_184") (pintype "passive+no_connect"))
    )
    (net (code "110") (name "unconnected-(J15-Pad185)") (class "Default")
      (node (ref "J15") (pin "185") (pinfunction "185_185") (pintype "passive+no_connect"))
    )
    (net (code "111") (name "unconnected-(J15-Pad186)") (class "Default")
      (node (ref "J15") (pin "186") (pinfunction "186_186") (pintype "passive+no_connect"))
    )
    (net (code "112") (name "unconnected-(J15-Pad188)") (class "Default")
      (node (ref "J15") (pin "188") (pinfunction "188_188") (pintype "passive+no_connect"))
    )
    (net (code "113") (name "unconnected-(J15-Pad189)") (class "Default")
      (node (ref "J15") (pin "189") (pinfunction "189_189") (pintype "passive+no_connect"))
    )
    (net (code "114") (name "unconnected-(J15-Pad190)") (class "Default")
      (node (ref "J15") (pin "190") (pinfunction "190_190") (pintype "passive+no_connect"))
    )
    (net (code "115") (name "unconnected-(J15-Pad192)") (class "Default")
      (node (ref "J15") (pin "192") (pinfunction "192_192") (pintype "passive+no_connect"))
    )
    (net (code "116") (name "unconnected-(J15-Pad193)") (class "Default")
      (node (ref "J15") (pin "193") (pinfunction "193_193") (pintype "passive+no_connect"))
    )
    (net (code "117") (name "unconnected-(J15-Pad194)") (class "Default")
      (node (ref "J15") (pin "194") (pinfunction "194_194") (pintype "passive+no_connect"))
    )
    (net (code "118") (name "unconnected-(J15-Pad196)") (class "Default")
      (node (ref "J15") (pin "196") (pinfunction "196_196") (pintype "passive+no_connect"))
    )
    (net (code "119") (name "unconnected-(J15-Pad197)") (class "Default")
      (node (ref "J15") (pin "197") (pinfunction "197_197") (pintype "passive+no_connect"))
    )
    (net (code "120") (name "unconnected-(J15-Pad198)") (class "Default")
      (node (ref "J15") (pin "198") (pinfunction "198_198") (pintype "passive+no_connect"))
    )
    (net (code "121") (name "unconnected-(J15-Pad200)") (class "Default")
      (node (ref "J15") (pin "200") (pinfunction "200_200") (pintype "passive+no_connect"))
    )
    (net (code "122") (name "unconnected-(J15-Pad201)") (class "Default")
      (node (ref "J15") (pin "201") (pinfunction "201_201") (pintype "passive+no_connect"))
    )
    (net (code "123") (name "unconnected-(J15-Pad202)") (class "Default")
      (node (ref "J15") (pin "202") (pinfunction "202_202") (pintype "passive+no_connect"))
    )
    (net (code "124") (name "unconnected-(J15-Pad204)") (class "Default")
      (node (ref "J15") (pin "204") (pinfunction "204_204") (pintype "passive+no_connect"))
    )
    (net (code "125") (name "unconnected-(J15-Pad205)") (class "Default")
      (node (ref "J15") (pin "205") (pinfunction "205_205") (pintype "passive+no_connect"))
    )
    (net (code "126") (name "unconnected-(J15-Pad206)") (class "Default")
      (node (ref "J15") (pin "206") (pinfunction "206_206") (pintype "passive+no_connect"))
    )
    (net (code "127") (name "unconnected-(J15-Pad207)") (class "Default")
      (node (ref "J15") (pin "207") (pinfunction "207_207") (pintype "passive+no_connect"))
    )
    (net (code "128") (name "unconnected-(J15-Pad208)") (class "Default")
      (node (ref "J15") (pin "208") (pinfunction "208_208") (pintype "passive+no_connect"))
    )
    (net (code "129") (name "unconnected-(J15-Pad209)") (class "Default")
      (node (ref "J15") (pin "209") (pinfunction "209_209") (pintype "passive+no_connect"))
    )
    (net (code "130") (name "unconnected-(J15-Pad210)") (class "Default")
      (node (ref "J15") (pin "210") (pinfunction "210_210") (pintype "passive+no_connect"))
    )
    (net (code "131") (name "unconnected-(J15-Pad211)") (class "Default")
      (node (ref "J15") (pin "211") (pinfunction "211_211") (pintype "passive+no_connect"))
    )
    (net (code "132") (name "unconnected-(J15-Pad212)") (class "Default")
      (node (ref "J15") (pin "212") (pinfunction "212_212") (pintype "passive+no_connect"))
    )
    (net (code "133") (name "unconnected-(J15-Pad213)") (class "Default")
      (node (ref "J15") (pin "213") (pinfunction "213_213") (pintype "passive+no_connect"))
    )
    (net (code "134") (name "unconnected-(J15-Pad214)") (class "Default")
      (node (ref "J15") (pin "214") (pinfunction "214_214") (pintype "passive+no_connect"))
    )
    (net (code "135") (name "unconnected-(J15-Pad215)") (class "Default")
      (node (ref "J15") (pin "215") (pinfunction "215_215") (pintype "passive+no_connect"))
    )
    (net (code "136") (name "unconnected-(J15-Pad216)") (class "Default")
      (node (ref "J15") (pin "216") (pinfunction "216_216") (pintype "passive+no_connect"))
    )
    (net (code "137") (name "unconnected-(J15-Pad217)") (class "Default")
      (node (ref "J15") (pin "217") (pinfunction "217_217") (pintype "passive+no_connect"))
    )
    (net (code "138") (name "unconnected-(J15-Pad218)") (class "Default")
      (node (ref "J15") (pin "218") (pinfunction "218_218") (pintype "passive+no_connect"))
    )
    (net (code "139") (name "unconnected-(J15-Pad219)") (class "Default")
      (node (ref "J15") (pin "219") (pinfunction "219_219") (pintype "passive+no_connect"))
    )
    (net (code "140") (name "unconnected-(J15-Pad220)") (class "Default")
      (node (ref "J15") (pin "220") (pinfunction "220_220") (pintype "passive+no_connect"))
    )
    (net (code "141") (name "unconnected-(J15-Pad221)") (class "Default")
      (node (ref "J15") (pin "221") (pinfunction "221_221") (pintype "passive+no_connect"))
    )
    (net (code "142") (name "unconnected-(J15-Pad222)") (class "Default")
      (node (ref "J15") (pin "222") (pinfunction "222_222") (pintype "passive+no_connect"))
    )
    (net (code "143") (name "unconnected-(J15-Pad223)") (class "Default")
      (node (ref "J15") (pin "223") (pinfunction "223_223") (pintype "passive+no_connect"))
    )
    (net (code "144") (name "unconnected-(J15-Pad224)") (class "Default")
      (node (ref "J15") (pin "224") (pinfunction "224_224") (pintype "passive+no_connect"))
    )
    (net (code "145") (name "unconnected-(J15-Pad225)") (class "Default")
      (node (ref "J15") (pin "225") (pinfunction "225_225") (pintype "passive+no_connect"))
    )
    (net (code "146") (name "unconnected-(J15-Pad226)") (class "Default")
      (node (ref "J15") (pin "226") (pinfunction "226_226") (pintype "passive+no_connect"))
    )
    (net (code "147") (name "unconnected-(J15-Pad227)") (class "Default")
      (node (ref "J15") (pin "227") (pinfunction "227_227") (pintype "passive+no_connect"))
    )
    (net (code "148") (name "unconnected-(J15-Pad228)") (class "Default")
      (node (ref "J15") (pin "228") (pinfunction "228_228") (pintype "passive+no_connect"))
    )
    (net (code "149") (name "unconnected-(J15-Pad229)") (class "Default")
      (node (ref "J15") (pin "229") (pinfunction "229_229") (pintype "passive+no_connect"))
    )
    (net (code "150") (name "unconnected-(J15-Pad230)") (class "Default")
      (node (ref "J15") (pin "230") (pinfunction "230_230") (pintype "passive+no_connect"))
    )
    (net (code "151") (name "unconnected-(J15-Pad231)") (class "Default")
      (node (ref "J15") (pin "231") (pinfunction "231_231") (pintype "passive+no_connect"))
    )
    (net (code "152") (name "unconnected-(J15-Pad232)") (class "Default")
      (node (ref "J15") (pin "232") (pinfunction "232_232") (pintype "passive+no_connect"))
    )
    (net (code "153") (name "unconnected-(J15-Pad233)") (class "Default")
      (node (ref "J15") (pin "233") (pinfunction "233_233") (pintype "passive+no_connect"))
    )
    (net (code "154") (name "unconnected-(J15-Pad234)") (class "Default")
      (node (ref "J15") (pin "234") (pinfunction "234_234") (pintype "passive+no_connect"))
    )
    (net (code "155") (name "unconnected-(J15-Pad235)") (class "Default")
      (node (ref "J15") (pin "235") (pinfunction "235_235") (pintype "passive+no_connect"))
    )
    (net (code "156") (name "unconnected-(J15-Pad236)") (class "Default")
      (node (ref "J15") (pin "236") (pinfunction "236_236") (pintype "passive+no_connect"))
    )
    (net (code "157") (name "unconnected-(J15-Pad237)") (class "Default")
      (node (ref "J15") (pin "237") (pinfunction "237_237") (pintype "passive+no_connect"))
    )
    (net (code "158") (name "unconnected-(J15-Pad238)") (class "Default")
      (node (ref "J15") (pin "238") (pinfunction "238_238") (pintype "passive+no_connect"))
    )
    (net (code "159") (name "unconnected-(J15-Pad239)") (class "Default")
      (node (ref "J15") (pin "239") (pinfunction "239_239") (pintype "passive+no_connect"))
    )
    (net (code "160") (name "unconnected-(J15-Pad240)") (class "Default")
      (node (ref "J15") (pin "240") (pinfunction "240_240") (pintype "passive+no_connect"))
    )
    (net (code "161") (name "unconnected-(J15-Pad241)") (class "Default")
      (node (ref "J15") (pin "241") (pinfunction "241_241") (pintype "passive+no_connect"))
    )
    (net (code "162") (name "unconnected-(J15-Pad242)") (class "Default")
      (node (ref "J15") (pin "242") (pinfunction "242_242") (pintype "passive+no_connect"))
    )
    (net (code "163") (name "unconnected-(J15-Pad243)") (class "Default")
      (node (ref "J15") (pin "243") (pinfunction "243_243") (pintype "passive+no_connect"))
    )
    (net (code "164") (name "unconnected-(J15-Pad244)") (class "Default")
      (node (ref "J15") (pin "244") (pinfunction "244_244") (pintype "passive+no_connect"))
    )
    (net (code "165") (name "unconnected-(J15-Pad245)") (class "Default")
      (node (ref "J15") (pin "245") (pinfunction "245_245") (pintype "passive+no_connect"))
    )
    (net (code "166") (name "unconnected-(J15-Pad246)") (class "Default")
      (node (ref "J15") (pin "246") (pinfunction "246_246") (pintype "passive+no_connect"))
    )
    (net (code "167") (name "unconnected-(J15-Pad247)") (class "Default")
      (node (ref "J15") (pin "247") (pinfunction "247_247") (pintype "passive+no_connect"))
    )
    (net (code "168") (name "unconnected-(J15-Pad248)") (class "Default")
      (node (ref "J15") (pin "248") (pinfunction "248_248") (pintype "passive+no_connect"))
    )
    (net (code "169") (name "unconnected-(J15-Pad249)") (class "Default")
      (node (ref "J15") (pin "249") (pinfunction "249_249") (pintype "passive+no_connect"))
    )
    (net (code "170") (name "unconnected-(J15-Pad250)") (class "Default")
      (node (ref "J15") (pin "250") (pinfunction "250_250") (pintype "passive+no_connect"))
    )
    (net (code "171") (name "unconnected-(J15-Pad251)") (class "Default")
      (node (ref "J15") (pin "251") (pinfunction "251_251") (pintype "passive+no_connect"))
    )
    (net (code "172") (name "unconnected-(J15-Pad252)") (class "Default")
      (node (ref "J15") (pin "252") (pinfunction "252_252") (pintype "passive+no_connect"))
    )
    (net (code "173") (name "unconnected-(J15-Pad253)") (class "Default")
      (node (ref "J15") (pin "253") (pinfunction "253_253") (pintype "passive+no_connect"))
    )
    (net (code "174") (name "unconnected-(J15-Pad254)") (class "Default")
      (node (ref "J15") (pin "254") (pinfunction "254_254") (pintype "passive+no_connect"))
    )
    (net (code "175") (name "unconnected-(J15-Pad255)") (class "Default")
      (node (ref "J15") (pin "255") (pinfunction "255_255") (pintype "passive+no_connect"))
    )
    (net (code "176") (name "unconnected-(J15-Pad256)") (class "Default")
      (node (ref "J15") (pin "256") (pinfunction "256_256") (pintype "passive+no_connect"))
    )
    (net (code "177") (name "unconnected-(J15-Pad257)") (class "Default")
      (node (ref "J15") (pin "257") (pinfunction "257_257") (pintype "passive+no_connect"))
    )
    (net (code "178") (name "unconnected-(J15-Pad258)") (class "Default")
      (node (ref "J15") (pin "258") (pinfunction "258_258") (pintype "passive+no_connect"))
    )
    (net (code "179") (name "unconnected-(J15-Pad259)") (class "Default")
      (node (ref "J15") (pin "259") (pinfunction "259_259") (pintype "passive+no_connect"))
    )
    (net (code "180") (name "unconnected-(J15-Pad260)") (class "Default")
      (node (ref "J15") (pin "260") (pinfunction "260_260") (pintype "passive+no_connect"))
    )
  )
)
